# Mic_Circuit.net
KiCad netlist of a schematic drawn in Altium Designer
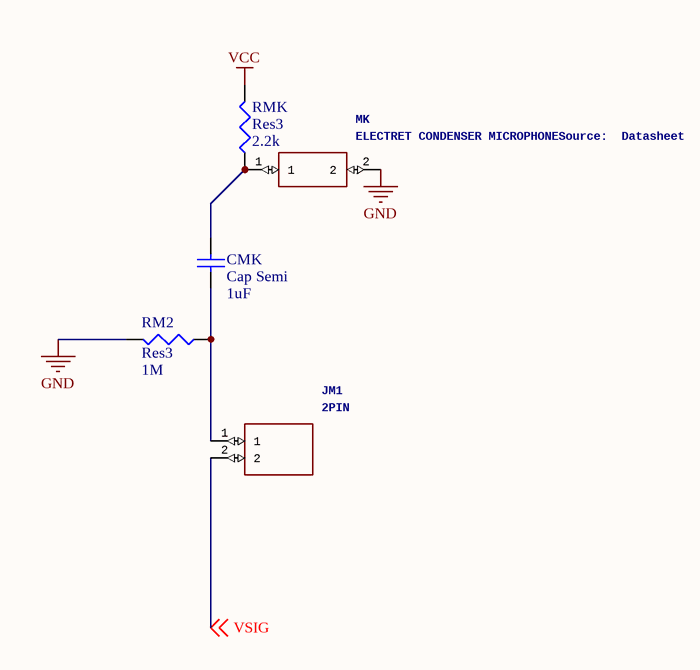
[diagram p0: Mic_Circuit.SchDoc]

(export (version "E")
  (design (tool "Eeschema 10.0.6"))
  (components
    (comp (ref "CMK")
      (value "Cap Semi")
      (footprint "1608[0603]")
      (description "Capacitor (Semiconductor SIM Model)")
      (fields (field (name "ALTIUM_VALUE") "1uF") (field (name "PUBLISHER") "Altium Limited"))
      (libsource (lib "Miscellaneous Devices") (part "Cap Semi"))
    )
    (comp (ref "JM1")
      (value "2PIN")
      (footprint "HDRV2W110P0X254_1X2_508X254X85")
      (fields
        (field (name "MANUFACTURER_PART_NUMBER") "61300211121")
        (field (name "RS_PART_NUMBER") "8281581P")
      )
      (libsource (lib "61300211121") (part "61300211121"))
    )
    (comp (ref "MK")
      (value "ELECTRET CONDENSER MICROPHONESource:  Datasheet")
      (footprint "CMA-4544PF-W")
      (fields (field (name "MANUFACTURER_PART_NUMBER") "CMA-4544PF-W"))
      (libsource (lib "CMA-4544PF-W") (part "CMA-4544PF-W"))
    )
    (comp (ref "RM2")
      (value "Res3")
      (footprint "1608[0603]")
      (description "Resistor")
      (fields (field (name "ALTIUM_VALUE") "1M") (field (name "PUBLISHER") "Altium Limited"))
      (libsource (lib "Miscellaneous Devices") (part "Res3"))
    )
    (comp (ref "RMK")
      (value "Res3")
      (footprint "1608[0603]")
      (description "Resistor")
      (fields (field (name "ALTIUM_VALUE") "2.2k") (field (name "PUBLISHER") "Altium Limited"))
      (libsource (lib "Miscellaneous Devices") (part "Res3"))
    )
  )
  (nets
    (net (code "1") (name "GND") (class "Default")
      (node (ref "MK") (pin "2") (pinfunction "2_2") (pintype "bidirectional"))
      (node (ref "RM2") (pin "1") (pinfunction "1_1") (pintype "passive"))
    )
    (net (code "2") (name "Net-(CMK-Pad1)") (class "Default")
      (node (ref "CMK") (pin "1") (pinfunction "1_1") (pintype "passive"))
      (node (ref "JM1") (pin "1") (pinfunction "1_1") (pintype "bidirectional"))
      (node (ref "RM2") (pin "2") (pinfunction "2_2") (pintype "passive"))
    )
    (net (code "3") (name "Net-(CMK-Pad2)") (class "Default")
      (node (ref "CMK") (pin "2") (pinfunction "2_2") (pintype "passive"))
      (node (ref "MK") (pin "1") (pinfunction "1_1") (pintype "bidirectional"))
      (node (ref "RMK") (pin "2") (pinfunction "2_2") (pintype "passive"))
    )
    (net (code "4") (name "VCC") (class "Default")
      (node (ref "RMK") (pin "1") (pinfunction "1_1") (pintype "passive"))
    )
    (net (code "5") (name "VSIG") (class "Default")
      (node (ref "JM1") (pin "2") (pinfunction "2_2") (pintype "bidirectional"))
    )
  )
)
